# 0Watt.net
KiCad netlist of a schematic drawn in EAGLE
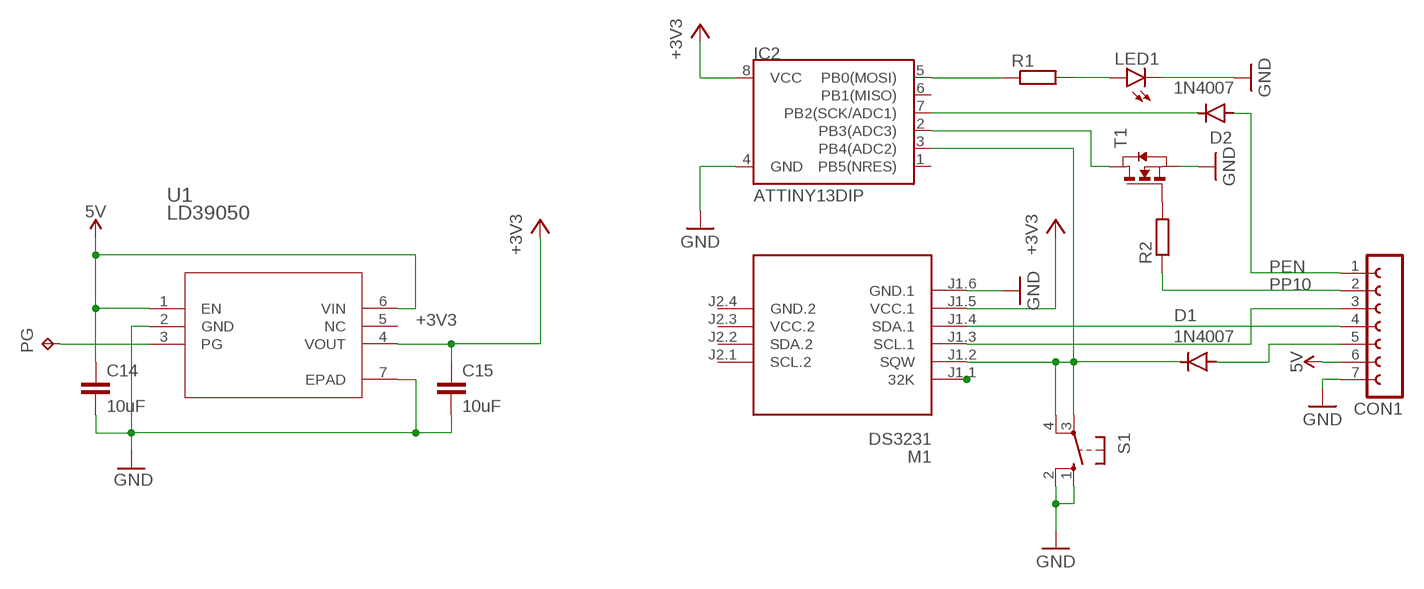
[diagram p0: schematic, sheet 1]

(export (version "E")
  (design (tool "Eeschema 10.0.6"))
  (components
    (comp (ref "C14")
      (value "10uF")
      (footprint "eagle-import:C1206")
      (libsource (lib "eagle-import") (part "C-EUC1206"))
    )
    (comp (ref "C15")
      (value "10uF")
      (footprint "eagle-import:C1206")
      (libsource (lib "eagle-import") (part "C-EUC1206"))
    )
    (comp (ref "CON1")
      (value "FE07-1")
      (footprint "eagle-import:FE07")
      (libsource (lib "eagle-import") (part "FE07-1"))
    )
    (comp (ref "D1")
      (value "1N4007")
      (footprint "eagle-import:DO-41")
      (fields
        (field (name "DIGIKEY_PART_NUMBER") "1N4007MSCT-ND")
        (field (name "MANUFACTURER") "Micro Commercial Co")
        (field (name "CREATED_BY") "PCBLayout.com")
      )
      (libsource (lib "eagle-import") (part "1N4007"))
    )
    (comp (ref "D2")
      (value "1N4007")
      (footprint "eagle-import:DO-41")
      (fields
        (field (name "DIGIKEY_PART_NUMBER") "1N4007MSCT-ND")
        (field (name "MANUFACTURER") "Micro Commercial Co")
        (field (name "CREATED_BY") "PCBLayout.com")
      )
      (libsource (lib "eagle-import") (part "1N4007"))
    )
    (comp (ref "IC2")
      (value "ATTINY13DIP")
      (footprint "eagle-import:DIP08_MCU")
      (libsource (lib "eagle-import") (part "ATTINY13DIP"))
    )
    (comp (ref "LED1")
      (value "LED5MM")
      (footprint "eagle-import:LED5MM")
      (libsource (lib "eagle-import") (part "LED5MM"))
    )
    (comp (ref "M1")
      (value "DS3231")
      (footprint "eagle-import:RTC-DS3231-AT24C32")
      (libsource (lib "eagle-import") (part "RTC-DS3231-AT24C32"))
    )
    (comp (ref "PG")
      (value "TPB2,54")
      (footprint "eagle-import:B2,54")
      (libsource (lib "eagle-import") (part "TPB2,54"))
    )
    (comp (ref "R1")
      (value "R-EU_0204/7")
      (footprint "eagle-import:0204_7")
      (libsource (lib "eagle-import") (part "R-EU_0204/7"))
    )
    (comp (ref "R2")
      (value "R-EU_R0805")
      (footprint "eagle-import:R0805")
      (libsource (lib "eagle-import") (part "R-EU_R0805"))
    )
    (comp (ref "S1")
      (value "10-XX")
      (footprint "eagle-import:B3F-10XX")
      (fields (field (name "MPN") "B3F-1000"))
      (libsource (lib "eagle-import") (part "10-XX"))
    )
    (comp (ref "T1")
      (value "NMOSSOT23")
      (footprint "eagle-import:SOT-23")
      (libsource (lib "eagle-import") (part "NMOSSOT23"))
    )
    (comp (ref "U1")
      (value "LD39050")
      (footprint "eagle-import:DFN6_3X3_STM-M")
      (fields
        (field (name "MANUFACTURER_PART_NUMBER") "LD39050PU33R")
        (field (name "COPYRIGHT") "Copyright (C) 2018 Accelerated Designs. All rights reserved")
      )
      (libsource (lib "eagle-import") (part "LD39050PU33RDFN6_3X3_STM-M"))
    )
  )
  (nets
    (net (code "1") (name "+3V3") (class "Default")
      (node (ref "C15") (pin "1") (pinfunction "1_1") (pintype "passive"))
      (node (ref "IC2") (pin "8") (pinfunction "VCC_8") (pintype "bidirectional"))
      (node (ref "M1") (pin "J1.5") (pinfunction "VCC.1_J1.5") (pintype "power_in"))
      (node (ref "U1") (pin "4") (pinfunction "VOUT_4") (pintype "output"))
    )
    (net (code "2") (name "/GND.2") (class "Default")
      (node (ref "M1") (pin "J2.4") (pinfunction "GND.2_J2.4") (pintype "power_in"))
    )
    (net (code "3") (name "/PEN") (class "Default")
      (node (ref "CON1") (pin "1") (pinfunction "1_1") (pintype "passive"))
      (node (ref "D2") (pin "A") (pinfunction "A_A") (pintype "passive"))
    )
    (net (code "4") (name "/PP10") (class "Default")
      (node (ref "CON1") (pin "2") (pinfunction "2_2") (pintype "passive"))
      (node (ref "R2") (pin "1") (pinfunction "1_1") (pintype "passive"))
    )
    (net (code "5") (name "/VCC.2") (class "Default")
      (node (ref "M1") (pin "J2.3") (pinfunction "VCC.2_J2.3") (pintype "power_in"))
    )
    (net (code "6") (name "5V") (class "Default")
      (node (ref "C14") (pin "1") (pinfunction "1_1") (pintype "passive"))
      (node (ref "CON1") (pin "6") (pinfunction "6_6") (pintype "passive"))
      (node (ref "U1") (pin "1") (pinfunction "EN_1") (pintype "input"))
      (node (ref "U1") (pin "6") (pinfunction "VIN_6") (pintype "input"))
    )
    (net (code "7") (name "GND") (class "Default")
      (node (ref "C14") (pin "2") (pinfunction "2_2") (pintype "passive"))
      (node (ref "C15") (pin "2") (pinfunction "2_2") (pintype "passive"))
      (node (ref "CON1") (pin "7") (pinfunction "7_7") (pintype "passive"))
      (node (ref "IC2") (pin "4") (pinfunction "GND_4") (pintype "bidirectional"))
      (node (ref "LED1") (pin "K") (pinfunction "C_K") (pintype "passive"))
      (node (ref "M1") (pin "J1.6") (pinfunction "GND.1_J1.6") (pintype "power_in"))
      (node (ref "S1") (pin "1") (pinfunction "S_1") (pintype "passive"))
      (node (ref "S1") (pin "2") (pinfunction "S1_2") (pintype "passive"))
      (node (ref "T1") (pin "2") (pinfunction "S_2") (pintype "passive"))
      (node (ref "U1") (pin "2") (pinfunction "GND_2") (pintype "power_in"))
      (node (ref "U1") (pin "7") (pinfunction "EPAD_7") (pintype "passive"))
    )
    (net (code "8") (name "Net-(CON1-Pad5)") (class "Default")
      (node (ref "CON1") (pin "5") (pinfunction "5_5") (pintype "passive"))
      (node (ref "D1") (pin "A") (pinfunction "A_A") (pintype "passive"))
    )
    (net (code "9") (name "Net-(IC2-PB0(MOSI))") (class "Default")
      (node (ref "IC2") (pin "5") (pinfunction "PB0(MOSI)_5") (pintype "bidirectional"))
      (node (ref "R1") (pin "1") (pinfunction "1_1") (pintype "passive"))
    )
    (net (code "10") (name "Net-(IC2-PB2(SCK{slash}ADC1))") (class "Default")
      (node (ref "D2") (pin "C") (pinfunction "C_C") (pintype "passive"))
      (node (ref "IC2") (pin "7") (pinfunction "PB2(SCK/ADC1)_7") (pintype "bidirectional"))
    )
    (net (code "11") (name "Net-(IC2-PB3(ADC3))") (class "Default")
      (node (ref "IC2") (pin "2") (pinfunction "PB3(ADC3)_2") (pintype "bidirectional"))
      (node (ref "T1") (pin "1") (pinfunction "D_1") (pintype "passive"))
    )
    (net (code "12") (name "Net-(IC2-PB4(ADC2))") (class "Default")
      (node (ref "D1") (pin "C") (pinfunction "C_C") (pintype "passive"))
      (node (ref "IC2") (pin "3") (pinfunction "PB4(ADC2)_3") (pintype "bidirectional"))
      (node (ref "M1") (pin "J1.2") (pinfunction "SQW_J1.2") (pintype "bidirectional"))
      (node (ref "S1") (pin "3") (pinfunction "P_3") (pintype "passive"))
      (node (ref "S1") (pin "4") (pinfunction "P1_4") (pintype "passive"))
    )
    (net (code "13") (name "Net-(LED1-PadA)") (class "Default")
      (node (ref "LED1") (pin "A") (pinfunction "A_A") (pintype "passive"))
      (node (ref "R1") (pin "2") (pinfunction "2_2") (pintype "passive"))
    )
    (net (code "14") (name "Net-(M1-SCL.1)") (class "Default")
      (node (ref "CON1") (pin "3") (pinfunction "3_3") (pintype "passive"))
      (node (ref "M1") (pin "J1.3") (pinfunction "SCL.1_J1.3") (pintype "bidirectional"))
    )
    (net (code "15") (name "Net-(M1-SDA.1)") (class "Default")
      (node (ref "CON1") (pin "4") (pinfunction "4_4") (pintype "passive"))
      (node (ref "M1") (pin "J1.4") (pinfunction "SDA.1_J1.4") (pintype "bidirectional"))
    )
    (net (code "16") (name "Net-(T1-G)") (class "Default")
      (node (ref "R2") (pin "2") (pinfunction "2_2") (pintype "passive"))
      (node (ref "T1") (pin "3") (pinfunction "G_3") (pintype "passive"))
    )
    (net (code "17") (name "Net-(U1-PG)") (class "Default")
      (node (ref "PG") (pin "TP") (pinfunction "TP_TP") (pintype "input"))
      (node (ref "U1") (pin "3") (pinfunction "PG_3") (pintype "passive"))
    )
    (net (code "18") (name "unconnected-(IC2-PB1(MISO)-Pad6)") (class "Default")
      (node (ref "IC2") (pin "6") (pinfunction "PB1(MISO)_6") (pintype "bidirectional"))
    )
    (net (code "19") (name "unconnected-(IC2-PB5(NRES)-Pad1)") (class "Default")
      (node (ref "IC2") (pin "1") (pinfunction "PB5(NRES)_1") (pintype "bidirectional"))
    )
    (net (code "20") (name "unconnected-(M1-32K-PadJ1.1)") (class "Default")
      (node (ref "M1") (pin "J1.1") (pinfunction "32K_J1.1") (pintype "bidirectional"))
    )
    (net (code "21") (name "unconnected-(M1-SCL.2-PadJ2.1)") (class "Default")
      (node (ref "M1") (pin "J2.1") (pinfunction "SCL.2_J2.1") (pintype "bidirectional"))
    )
    (net (code "22") (name "unconnected-(M1-SDA.2-PadJ2.2)") (class "Default")
      (node (ref "M1") (pin "J2.2") (pinfunction "SDA.2_J2.2") (pintype "bidirectional"))
    )
    (net (code "23") (name "unconnected-(U1-NC-Pad5)") (class "Default")
      (node (ref "U1") (pin "5") (pinfunction "NC_5") (pintype "no_connect"))
    )
  )
)
